# DIGITAL_DATA.net
KiCad netlist of a schematic drawn in Altium Designer
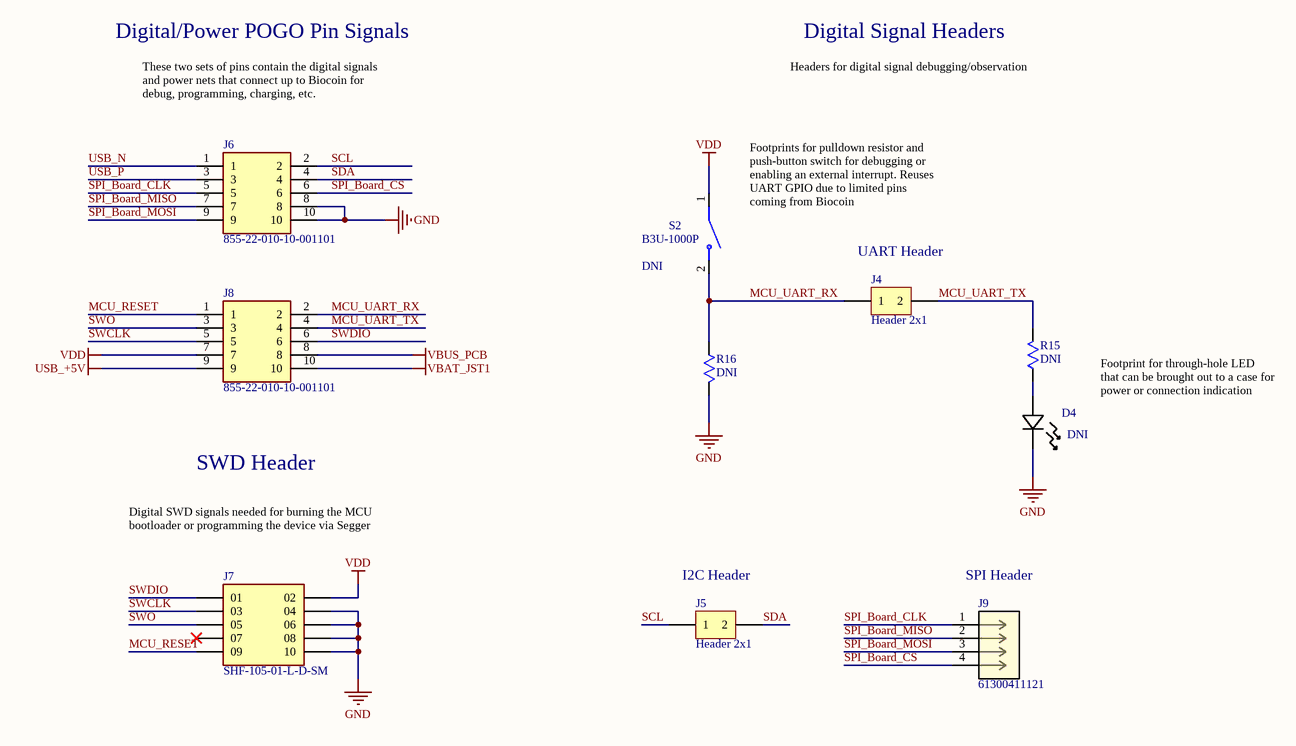
[diagram p0: DIGITAL_DATA.SchDoc]

(export (version "E")
  (design (tool "Eeschema 10.0.6"))
  (components
    (comp (ref "D4")
      (value "SLI-343V8RC3F")
      (footprint "LED_SLI-343D_ROM")
      (description "No Description Available")
      (fields
        (field (name "DO NOT INSTALL") "DNI")
        (field (name "COPYRIGHT") "Copyright (C) 2018 Accelerated Designs. All rights reserved")
      )
      (libsource (lib "Schlib") (part "SLI-343V8RC3F"))
    )
    (comp (ref "J4")
      (value "Header 2x1")
      (footprint "Header 1x2")
      (description "Pin Header 2x1")
      (fields (field (name "DESIGNER") "OMIGA"))
      (libsource (lib "Schlib") (part "Header 2x1"))
    )
    (comp (ref "J5")
      (value "Header 2x1")
      (footprint "Header 1x2")
      (description "Pin Header 2x1")
      (fields (field (name "DESIGNER") "OMIGA"))
      (libsource (lib "Schlib") (part "Header 2x1"))
    )
    (comp (ref "J6")
      (value "855-22-010-10-001101")
      (footprint "HDRV10W41P127_2X5_927X300X627P")
      (libsource (lib "Schlib") (part "10 pin Pogo Pin Male Header"))
    )
    (comp (ref "J7")
      (value "SHF-105-01-L-D-SM")
      (footprint "SAMTEC_SHF-105-01-L-D-SM")
      (description "SHF - Samtec Wire-to-Board 1.27mm Surface Mount Shrouded Header")
      (fields (field (name "MF") "Samtec") (field (name "DIGI-KEY_PART_NUMBER") "SAM10710-ND"))
      (libsource (lib "Schlib") (part "SHF-105-01-L-D-SM"))
    )
    (comp (ref "J8")
      (value "855-22-010-10-001101")
      (footprint "HDRV10W41P127_2X5_927X300X627P")
      (libsource (lib "Schlib") (part "10 pin Pogo Pin Male Header"))
    )
    (comp (ref "J9")
      (value "61300411121")
      (footprint "CONN_61300411121_WRE")
      (description "CONN HEADER VERT 4POS 2.54MM")
      (libsource (lib "Schlib") (part "Header 4x1"))
    )
    (comp (ref "R15")
      (value "DNI")
      (footprint "0805-RES")
      (description "Surface Mount Resistor")
      (fields (field (name "Comment") "RES") (field (name "DESIGNER") "OMIGA"))
      (libsource (lib "Schlib") (part "RES SMD"))
    )
    (comp (ref "R16")
      (value "DNI")
      (footprint "0805-RES")
      (description "Surface Mount Resistor")
      (fields (field (name "Comment") "RES") (field (name "DESIGNER") "OMIGA"))
      (libsource (lib "Schlib") (part "RES SMD"))
    )
    (comp (ref "S2")
      (value "B3U-1000P")
      (footprint "SW_B3U-1000P")
      (description "SWITCH TACTILE SPST-NO 0.05A 12V")
      (fields (field (name "DO NOT INSTALL") "DNI"))
      (libsource (lib "Schlib") (part "Pushbutton Small"))
    )
  )
  (nets
    (net (code "1") (name "/MCU_RESET") (class "Default")
      (node (ref "J7") (pin "09") (pinfunction "09_09") (pintype "passive"))
      (node (ref "J8") (pin "1") (pinfunction "1_1") (pintype "passive"))
    )
    (net (code "2") (name "/MCU_UART_RX") (class "Default")
      (node (ref "J4") (pin "1") (pinfunction "1_1") (pintype "passive"))
      (node (ref "J8") (pin "2") (pinfunction "2_2") (pintype "passive"))
      (node (ref "R16") (pin "1") (pinfunction "1_1") (pintype "passive"))
      (node (ref "S2") (pin "2") (pinfunction "2_2") (pintype "passive"))
    )
    (net (code "3") (name "/MCU_UART_TX") (class "Default")
      (node (ref "J4") (pin "2") (pinfunction "2_2") (pintype "passive"))
      (node (ref "J8") (pin "4") (pinfunction "4_4") (pintype "passive"))
      (node (ref "R15") (pin "2") (pinfunction "2_2") (pintype "passive"))
    )
    (net (code "4") (name "/SCL") (class "Default")
      (node (ref "J5") (pin "1") (pinfunction "1_1") (pintype "passive"))
      (node (ref "J6") (pin "2") (pinfunction "2_2") (pintype "passive"))
    )
    (net (code "5") (name "/SDA") (class "Default")
      (node (ref "J5") (pin "2") (pinfunction "2_2") (pintype "passive"))
      (node (ref "J6") (pin "4") (pinfunction "4_4") (pintype "passive"))
    )
    (net (code "6") (name "/SPI_Board_CLK") (class "Default")
      (node (ref "J6") (pin "5") (pinfunction "5_5") (pintype "passive"))
      (node (ref "J9") (pin "1") (pinfunction "1_1") (pintype "passive"))
    )
    (net (code "7") (name "/SPI_Board_CS") (class "Default")
      (node (ref "J6") (pin "6") (pinfunction "6_6") (pintype "passive"))
      (node (ref "J9") (pin "4") (pinfunction "4_4") (pintype "passive"))
    )
    (net (code "8") (name "/SPI_Board_MISO") (class "Default")
      (node (ref "J6") (pin "7") (pinfunction "7_7") (pintype "passive"))
      (node (ref "J9") (pin "2") (pinfunction "2_2") (pintype "passive"))
    )
    (net (code "9") (name "/SPI_Board_MOSI") (class "Default")
      (node (ref "J6") (pin "9") (pinfunction "9_9") (pintype "passive"))
      (node (ref "J9") (pin "3") (pinfunction "3_3") (pintype "passive"))
    )
    (net (code "10") (name "/SWCLK") (class "Default")
      (node (ref "J7") (pin "03") (pinfunction "03_03") (pintype "passive"))
      (node (ref "J8") (pin "5") (pinfunction "5_5") (pintype "passive"))
    )
    (net (code "11") (name "/SWDIO") (class "Default")
      (node (ref "J7") (pin "01") (pinfunction "01_01") (pintype "passive"))
      (node (ref "J8") (pin "6") (pinfunction "6_6") (pintype "passive"))
    )
    (net (code "12") (name "/SWO") (class "Default")
      (node (ref "J7") (pin "05") (pinfunction "05_05") (pintype "passive"))
      (node (ref "J8") (pin "3") (pinfunction "3_3") (pintype "passive"))
    )
    (net (code "13") (name "/USB_N") (class "Default")
      (node (ref "J6") (pin "1") (pinfunction "1_1") (pintype "passive"))
    )
    (net (code "14") (name "/USB_P") (class "Default")
      (node (ref "J6") (pin "3") (pinfunction "3_3") (pintype "passive"))
    )
    (net (code "15") (name "GND") (class "Default")
      (node (ref "D4") (pin "1") (pinfunction "1_1") (pintype "passive"))
      (node (ref "J6") (pin "10") (pinfunction "10_10") (pintype "passive"))
      (node (ref "J6") (pin "8") (pinfunction "8_8") (pintype "passive"))
      (node (ref "J7") (pin "04") (pinfunction "04_04") (pintype "passive"))
      (node (ref "J7") (pin "06") (pinfunction "06_06") (pintype "passive"))
      (node (ref "J7") (pin "08") (pinfunction "08_08") (pintype "passive"))
      (node (ref "J7") (pin "10") (pinfunction "10_10") (pintype "passive"))
      (node (ref "R16") (pin "2") (pinfunction "2_2") (pintype "passive"))
    )
    (net (code "16") (name "Net-(D4-Pad2)") (class "Default")
      (node (ref "D4") (pin "2") (pinfunction "2_2") (pintype "passive"))
      (node (ref "R15") (pin "1") (pinfunction "1_1") (pintype "passive"))
    )
    (net (code "17") (name "USB_+5V") (class "Default")
      (node (ref "J8") (pin "9") (pinfunction "9_9") (pintype "passive"))
    )
    (net (code "18") (name "VBAT_JST1") (class "Default")
      (node (ref "J8") (pin "10") (pinfunction "10_10") (pintype "passive"))
    )
    (net (code "19") (name "VBUS_PCB") (class "Default")
      (node (ref "J8") (pin "8") (pinfunction "8_8") (pintype "passive"))
    )
    (net (code "20") (name "VDD") (class "Default")
      (node (ref "J7") (pin "02") (pinfunction "02_02") (pintype "passive"))
      (node (ref "J8") (pin "7") (pinfunction "7_7") (pintype "passive"))
      (node (ref "S2") (pin "1") (pinfunction "1_1") (pintype "passive"))
    )
    (net (code "21") (name "unconnected-(J7-Pad07)") (class "Default")
      (node (ref "J7") (pin "07") (pinfunction "07_07") (pintype "passive+no_connect"))
    )
  )
)
